# Fastino_FPGA_Supply.net
KiCad netlist of a schematic drawn in Altium Designer
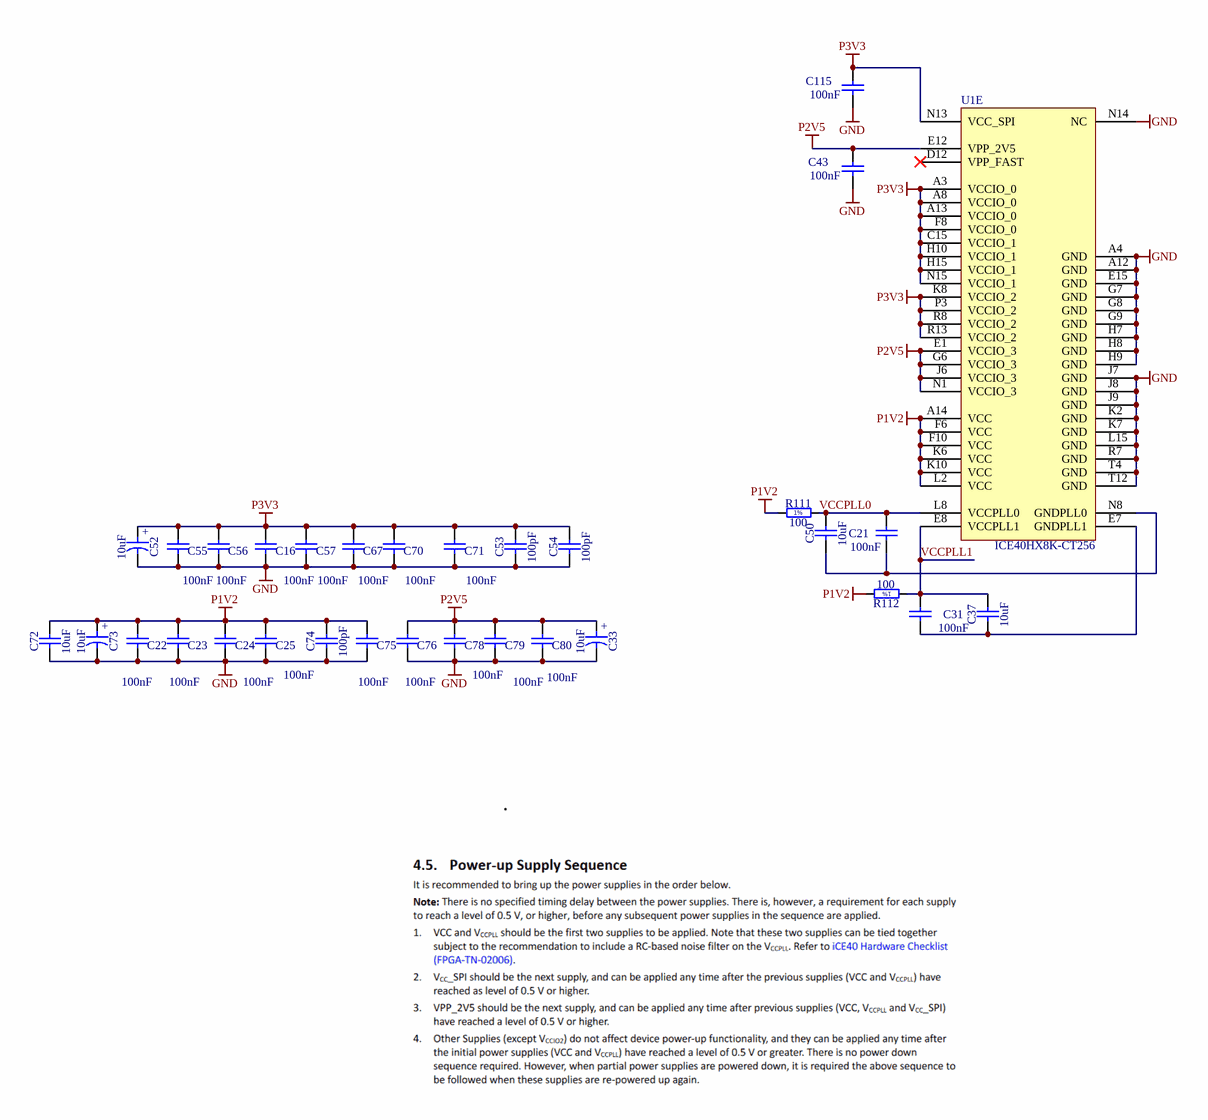
[diagram p0: Fastino_FPGA_Supply.SchDoc]

(export (version "E")
  (design (tool "Eeschema 10.0.6"))
  (components
    (comp (ref "C16")
      (value "100nF")
      (footprint "CAPC1005X55N")
      (description "Non-polarised capacitor")
      (fields
        (field (name "PART NUMBER") "CC0402_100NF_16V_10%_X5R")
        (field (name "VOLTAGE") "16V")
        (field (name "AUTHOR") "CERN DEM JLC")
      )
      (libsource (lib "Capacitors") (part "Capacitor - non polarized"))
    )
    (comp (ref "C21")
      (value "100nF")
      (footprint "CAPC1005X55N")
      (description "Non-polarised capacitor")
      (fields
        (field (name "PART NUMBER") "CC0402_100NF_16V_10%_X5R")
        (field (name "VOLTAGE") "16V")
        (field (name "AUTHOR") "CERN DEM JLC")
      )
      (libsource (lib "Capacitors") (part "Capacitor - non polarized"))
    )
    (comp (ref "C22")
      (value "100nF")
      (footprint "CAPC1005X55N")
      (description "Non-polarised capacitor")
      (fields
        (field (name "PART NUMBER") "CC0402_100NF_16V_10%_X5R")
        (field (name "VOLTAGE") "16V")
        (field (name "AUTHOR") "CERN DEM JLC")
      )
      (libsource (lib "Capacitors") (part "Capacitor - non polarized"))
    )
    (comp (ref "C23")
      (value "100nF")
      (footprint "CAPC1005X55N")
      (description "Non-polarised capacitor")
      (fields
        (field (name "PART NUMBER") "CC0402_100NF_16V_10%_X5R")
        (field (name "VOLTAGE") "16V")
        (field (name "AUTHOR") "CERN DEM JLC")
      )
      (libsource (lib "Capacitors") (part "Capacitor - non polarized"))
    )
    (comp (ref "C24")
      (value "100nF")
      (footprint "CAPC1005X55N")
      (description "Non-polarised capacitor")
      (fields
        (field (name "PART NUMBER") "CC0402_100NF_16V_10%_X5R")
        (field (name "VOLTAGE") "16V")
        (field (name "AUTHOR") "CERN DEM JLC")
      )
      (libsource (lib "Capacitors") (part "Capacitor - non polarized"))
    )
    (comp (ref "C25")
      (value "100nF")
      (footprint "CAPC1005X55N")
      (description "Non-polarised capacitor")
      (fields
        (field (name "PART NUMBER") "CC0402_100NF_16V_10%_X5R")
        (field (name "VOLTAGE") "16V")
        (field (name "AUTHOR") "CERN DEM JLC")
      )
      (libsource (lib "Capacitors") (part "Capacitor - non polarized"))
    )
    (comp (ref "C31")
      (value "100nF")
      (footprint "CAPC1005X55N")
      (description "Non-polarised capacitor")
      (fields
        (field (name "PART NUMBER") "CC0402_100NF_16V_10%_X5R")
        (field (name "VOLTAGE") "16V")
        (field (name "AUTHOR") "CERN DEM JLC")
      )
      (libsource (lib "Capacitors") (part "Capacitor - non polarized"))
    )
    (comp (ref "C33")
      (value "10uF")
      (footprint "CAPMP3216X180N")
      (description "Polarised capacitor")
      (fields
        (field (name "PART NUMBER") "CTE3216-18_10UF_16V_20%_AVX_TCJ")
        (field (name "VOLTAGE") "16V")
        (field (name "AUTHOR") "CERN DEM JLC")
      )
      (libsource (lib "Capacitors") (part "Capacitor - polarized"))
    )
    (comp (ref "C37")
      (value "10uF")
      (footprint "CAPC1005X70N")
      (description "Non-polarised capacitor")
      (fields
        (field (name "PART NUMBER") "CC0402_10UF_6.3V_20%_X5R")
        (field (name "VOLTAGE") "6.3V")
        (field (name "AUTHOR") "CERN DEM JLC")
      )
      (libsource (lib "Capacitors") (part "Capacitor - non polarized"))
    )
    (comp (ref "C43")
      (value "100nF")
      (footprint "CAPC1005X55N")
      (description "Non-polarised capacitor")
      (fields
        (field (name "PART NUMBER") "CC0402_100NF_16V_10%_X5R")
        (field (name "VOLTAGE") "16V")
        (field (name "AUTHOR") "CERN DEM JLC")
      )
      (libsource (lib "Capacitors") (part "Capacitor - non polarized"))
    )
    (comp (ref "C50")
      (value "10uF")
      (footprint "CAPC1005X70N")
      (description "Non-polarised capacitor")
      (fields
        (field (name "PART NUMBER") "CC0402_10UF_6.3V_20%_X5R")
        (field (name "VOLTAGE") "6.3V")
        (field (name "AUTHOR") "CERN DEM JLC")
      )
      (libsource (lib "Capacitors") (part "Capacitor - non polarized"))
    )
    (comp (ref "C52")
      (value "10uF")
      (footprint "CAPMP3216X180N")
      (description "Polarised capacitor")
      (fields
        (field (name "PART NUMBER") "CTE3216-18_10UF_16V_20%_AVX_TCJ")
        (field (name "VOLTAGE") "16V")
        (field (name "AUTHOR") "CERN DEM JLC")
      )
      (libsource (lib "Capacitors") (part "Capacitor - polarized"))
    )
    (comp (ref "C53")
      (value "100pF")
      (footprint "CAPC1005X55N")
      (description "Non-polarised capacitor")
      (fields
        (field (name "PART NUMBER") "CC0402_100PF_50V_5%_C0G")
        (field (name "VOLTAGE") "50V")
        (field (name "AUTHOR") "CERN DEM JLC")
      )
      (libsource (lib "Capacitors") (part "Capacitor - non polarized"))
    )
    (comp (ref "C54")
      (value "100pF")
      (footprint "CAPC1005X55N")
      (description "Non-polarised capacitor")
      (fields
        (field (name "PART NUMBER") "CC0402_100PF_50V_5%_C0G")
        (field (name "VOLTAGE") "50V")
        (field (name "AUTHOR") "CERN DEM JLC")
      )
      (libsource (lib "Capacitors") (part "Capacitor - non polarized"))
    )
    (comp (ref "C55")
      (value "100nF")
      (footprint "CAPC1005X55N")
      (description "Non-polarised capacitor")
      (fields
        (field (name "PART NUMBER") "CC0402_100NF_16V_10%_X5R")
        (field (name "VOLTAGE") "16V")
        (field (name "AUTHOR") "CERN DEM JLC")
      )
      (libsource (lib "Capacitors") (part "Capacitor - non polarized"))
    )
    (comp (ref "C56")
      (value "100nF")
      (footprint "CAPC1005X55N")
      (description "Non-polarised capacitor")
      (fields
        (field (name "PART NUMBER") "CC0402_100NF_16V_10%_X5R")
        (field (name "VOLTAGE") "16V")
        (field (name "AUTHOR") "CERN DEM JLC")
      )
      (libsource (lib "Capacitors") (part "Capacitor - non polarized"))
    )
    (comp (ref "C57")
      (value "100nF")
      (footprint "CAPC1005X55N")
      (description "Non-polarised capacitor")
      (fields
        (field (name "PART NUMBER") "CC0402_100NF_16V_10%_X5R")
        (field (name "VOLTAGE") "16V")
        (field (name "AUTHOR") "CERN DEM JLC")
      )
      (libsource (lib "Capacitors") (part "Capacitor - non polarized"))
    )
    (comp (ref "C67")
      (value "100nF")
      (footprint "CAPC1005X55N")
      (description "Non-polarised capacitor")
      (fields
        (field (name "PART NUMBER") "CC0402_100NF_16V_10%_X5R")
        (field (name "VOLTAGE") "16V")
        (field (name "AUTHOR") "CERN DEM JLC")
      )
      (libsource (lib "Capacitors") (part "Capacitor - non polarized"))
    )
    (comp (ref "C70")
      (value "100nF")
      (footprint "CAPC1005X55N")
      (description "Non-polarised capacitor")
      (fields
        (field (name "PART NUMBER") "CC0402_100NF_16V_10%_X5R")
        (field (name "VOLTAGE") "16V")
        (field (name "AUTHOR") "CERN DEM JLC")
      )
      (libsource (lib "Capacitors") (part "Capacitor - non polarized"))
    )
    (comp (ref "C71")
      (value "100nF")
      (footprint "CAPC1005X55N")
      (description "Non-polarised capacitor")
      (fields
        (field (name "PART NUMBER") "CC0402_100NF_16V_10%_X5R")
        (field (name "VOLTAGE") "16V")
        (field (name "AUTHOR") "CERN DEM JLC")
      )
      (libsource (lib "Capacitors") (part "Capacitor - non polarized"))
    )
    (comp (ref "C72")
      (value "10uF")
      (footprint "CAPC2012X135N")
      (description "Non-polarised capacitor")
      (fields
        (field (name "PART NUMBER") "CC0805_10UF_16V_10%_X5R")
        (field (name "VOLTAGE") "16V")
        (field (name "AUTHOR") "CERN DEM JLC")
      )
      (libsource (lib "Capacitors") (part "Capacitor - non polarized"))
    )
    (comp (ref "C73")
      (value "10uF")
      (footprint "CAPMP3216X180N")
      (description "Polarised capacitor")
      (fields
        (field (name "PART NUMBER") "CTE3216-18_10UF_16V_20%_AVX_TCJ")
        (field (name "VOLTAGE") "16V")
        (field (name "AUTHOR") "CERN DEM JLC")
      )
      (libsource (lib "Capacitors") (part "Capacitor - polarized"))
    )
    (comp (ref "C74")
      (value "100pF")
      (footprint "CAPC1005X55N")
      (description "Non-polarised capacitor")
      (fields
        (field (name "PART NUMBER") "CC0402_100PF_50V_5%_C0G")
        (field (name "VOLTAGE") "50V")
        (field (name "AUTHOR") "CERN DEM JLC")
      )
      (libsource (lib "Capacitors") (part "Capacitor - non polarized"))
    )
    (comp (ref "C75")
      (value "100nF")
      (footprint "CAPC1005X55N")
      (description "Non-polarised capacitor")
      (fields
        (field (name "PART NUMBER") "CC0402_100NF_16V_10%_X5R")
        (field (name "VOLTAGE") "16V")
        (field (name "AUTHOR") "CERN DEM JLC")
      )
      (libsource (lib "Capacitors") (part "Capacitor - non polarized"))
    )
    (comp (ref "C76")
      (value "100nF")
      (footprint "CAPC1005X55N")
      (description "Non-polarised capacitor")
      (fields
        (field (name "PART NUMBER") "CC0402_100NF_16V_10%_X5R")
        (field (name "VOLTAGE") "16V")
        (field (name "AUTHOR") "CERN DEM JLC")
      )
      (libsource (lib "Capacitors") (part "Capacitor - non polarized"))
    )
    (comp (ref "C78")
      (value "100nF")
      (footprint "CAPC1005X55N")
      (description "Non-polarised capacitor")
      (fields
        (field (name "PART NUMBER") "CC0402_100NF_16V_10%_X5R")
        (field (name "VOLTAGE") "16V")
        (field (name "AUTHOR") "CERN DEM JLC")
      )
      (libsource (lib "Capacitors") (part "Capacitor - non polarized"))
    )
    (comp (ref "C79")
      (value "100nF")
      (footprint "CAPC1005X55N")
      (description "Non-polarised capacitor")
      (fields
        (field (name "PART NUMBER") "CC0402_100NF_16V_10%_X5R")
        (field (name "VOLTAGE") "16V")
        (field (name "AUTHOR") "CERN DEM JLC")
      )
      (libsource (lib "Capacitors") (part "Capacitor - non polarized"))
    )
    (comp (ref "C80")
      (value "100nF")
      (footprint "CAPC1005X55N")
      (description "Non-polarised capacitor")
      (fields
        (field (name "PART NUMBER") "CC0402_100NF_16V_10%_X5R")
        (field (name "VOLTAGE") "16V")
        (field (name "AUTHOR") "CERN DEM JLC")
      )
      (libsource (lib "Capacitors") (part "Capacitor - non polarized"))
    )
    (comp (ref "C115")
      (value "100nF")
      (footprint "CAPC1005X55N")
      (description "Non-polarised capacitor")
      (fields
        (field (name "PART NUMBER") "CC0402_100NF_16V_10%_X5R")
        (field (name "VOLTAGE") "16V")
        (field (name "AUTHOR") "CERN DEM JLC")
      )
      (libsource (lib "Capacitors") (part "Capacitor - non polarized"))
    )
    (comp (ref "R111")
      (value "100")
      (footprint "RESC1005X40N")
      (description "Resistor - 1%")
      (fields
        (field (name "PART NUMBER") "R0402_100R_1%_0.0625W_100PPM")
        (field (name "POWER") "0.0625W")
        (field (name "AUTHOR") "CERN DEM JLC")
      )
      (libsource (lib "Resistors") (part "Resistor - 1%"))
    )
    (comp (ref "R112")
      (value "100")
      (footprint "RESC1005X40N")
      (description "Resistor - 1%")
      (fields
        (field (name "PART NUMBER") "R0402_100R_1%_0.0625W_100PPM")
        (field (name "POWER") "0.0625W")
        (field (name "AUTHOR") "CERN DEM JLC")
      )
      (libsource (lib "Resistors") (part "Resistor - 1%"))
    )
    (comp (ref "U1")
      (value "ICE40HX8K-CT256")
      (footprint "LATC-caBGA-256")
      (fields (field (name "MANUFACTURER") "Lattice Semiconductor"))
      (libsource (lib "Altium Content Vault") (part "LATC-HX8K-caBGA-256"))
    )
  )
  (nets
    (net (code "1") (name "/VCCPLL0") (class "Default")
      (node (ref "C21") (pin "2") (pinfunction "2_2") (pintype "passive"))
      (node (ref "C50") (pin "2") (pinfunction "2_2") (pintype "passive"))
      (node (ref "R111") (pin "2") (pinfunction "2_2") (pintype "passive"))
      (node (ref "U1") (pin "L8") (pinfunction "VCCPLL0_L8") (pintype "power_in"))
    )
    (net (code "2") (name "/VCCPLL1") (class "Default")
      (node (ref "C31") (pin "2") (pinfunction "2_2") (pintype "passive"))
      (node (ref "C37") (pin "2") (pinfunction "2_2") (pintype "passive"))
      (node (ref "R112") (pin "1") (pinfunction "1_1") (pintype "passive"))
      (node (ref "U1") (pin "E8") (pinfunction "VCCPLL1_E8") (pintype "power_in"))
    )
    (net (code "3") (name "GND") (class "Default")
      (node (ref "C115") (pin "1") (pinfunction "1_1") (pintype "passive"))
      (node (ref "C16") (pin "1") (pinfunction "1_1") (pintype "passive"))
      (node (ref "C22") (pin "1") (pinfunction "1_1") (pintype "passive"))
      (node (ref "C23") (pin "1") (pinfunction "1_1") (pintype "passive"))
      (node (ref "C24") (pin "1") (pinfunction "1_1") (pintype "passive"))
      (node (ref "C25") (pin "1") (pinfunction "1_1") (pintype "passive"))
      (node (ref "C33") (pin "2") (pinfunction "2_2") (pintype "passive"))
      (node (ref "C43") (pin "1") (pinfunction "1_1") (pintype "passive"))
      (node (ref "C52") (pin "2") (pinfunction "2_2") (pintype "passive"))
      (node (ref "C53") (pin "1") (pinfunction "1_1") (pintype "passive"))
      (node (ref "C54") (pin "1") (pinfunction "1_1") (pintype "passive"))
      (node (ref "C55") (pin "1") (pinfunction "1_1") (pintype "passive"))
      (node (ref "C56") (pin "1") (pinfunction "1_1") (pintype "passive"))
      (node (ref "C57") (pin "1") (pinfunction "1_1") (pintype "passive"))
      (node (ref "C67") (pin "1") (pinfunction "1_1") (pintype "passive"))
      (node (ref "C70") (pin "1") (pinfunction "1_1") (pintype "passive"))
      (node (ref "C71") (pin "1") (pinfunction "1_1") (pintype "passive"))
      (node (ref "C72") (pin "1") (pinfunction "1_1") (pintype "passive"))
      (node (ref "C73") (pin "2") (pinfunction "2_2") (pintype "passive"))
      (node (ref "C74") (pin "1") (pinfunction "1_1") (pintype "passive"))
      (node (ref "C75") (pin "1") (pinfunction "1_1") (pintype "passive"))
      (node (ref "C76") (pin "1") (pinfunction "1_1") (pintype "passive"))
      (node (ref "C78") (pin "1") (pinfunction "1_1") (pintype "passive"))
      (node (ref "C79") (pin "1") (pinfunction "1_1") (pintype "passive"))
      (node (ref "C80") (pin "1") (pinfunction "1_1") (pintype "passive"))
      (node (ref "U1") (pin "A12") (pinfunction "GND_A12") (pintype "power_in"))
      (node (ref "U1") (pin "A4") (pinfunction "GND_A4") (pintype "power_in"))
      (node (ref "U1") (pin "E15") (pinfunction "GND_E15") (pintype "power_in"))
      (node (ref "U1") (pin "G7") (pinfunction "GND_G7") (pintype "power_in"))
      (node (ref "U1") (pin "G8") (pinfunction "GND_G8") (pintype "power_in"))
      (node (ref "U1") (pin "G9") (pinfunction "GND_G9") (pintype "power_in"))
      (node (ref "U1") (pin "H7") (pinfunction "GND_H7") (pintype "power_in"))
      (node (ref "U1") (pin "H8") (pinfunction "GND_H8") (pintype "power_in"))
      (node (ref "U1") (pin "H9") (pinfunction "GND_H9") (pintype "power_in"))
      (node (ref "U1") (pin "J7") (pinfunction "GND_J7") (pintype "power_in"))
      (node (ref "U1") (pin "J8") (pinfunction "GND_J8") (pintype "power_in"))
      (node (ref "U1") (pin "J9") (pinfunction "GND_J9") (pintype "power_in"))
      (node (ref "U1") (pin "K2") (pinfunction "GND_K2") (pintype "power_in"))
      (node (ref "U1") (pin "K7") (pinfunction "GND_K7") (pintype "power_in"))
      (node (ref "U1") (pin "L15") (pinfunction "GND_L15") (pintype "power_in"))
      (node (ref "U1") (pin "N14") (pinfunction "NC_N14") (pintype "passive"))
      (node (ref "U1") (pin "R7") (pinfunction "GND_R7") (pintype "power_in"))
      (node (ref "U1") (pin "T12") (pinfunction "GND_T12") (pintype "power_in"))
      (node (ref "U1") (pin "T4") (pinfunction "GND_T4") (pintype "power_in"))
    )
    (net (code "4") (name "Net-(U1E-GNDPLL0)") (class "Default")
      (node (ref "C21") (pin "1") (pinfunction "1_1") (pintype "passive"))
      (node (ref "C50") (pin "1") (pinfunction "1_1") (pintype "passive"))
      (node (ref "U1") (pin "N8") (pinfunction "GNDPLL0_N8") (pintype "power_in"))
    )
    (net (code "5") (name "Net-(U1E-GNDPLL1)") (class "Default")
      (node (ref "C31") (pin "1") (pinfunction "1_1") (pintype "passive"))
      (node (ref "C37") (pin "1") (pinfunction "1_1") (pintype "passive"))
      (node (ref "U1") (pin "E7") (pinfunction "GNDPLL1_E7") (pintype "power_in"))
    )
    (net (code "6") (name "P1V2") (class "Default")
      (node (ref "C22") (pin "2") (pinfunction "2_2") (pintype "passive"))
      (node (ref "C23") (pin "2") (pinfunction "2_2") (pintype "passive"))
      (node (ref "C24") (pin "2") (pinfunction "2_2") (pintype "passive"))
      (node (ref "C25") (pin "2") (pinfunction "2_2") (pintype "passive"))
      (node (ref "C72") (pin "2") (pinfunction "2_2") (pintype "passive"))
      (node (ref "C73") (pin "1") (pinfunction "1_1") (pintype "passive"))
      (node (ref "C74") (pin "2") (pinfunction "2_2") (pintype "passive"))
      (node (ref "C75") (pin "2") (pinfunction "2_2") (pintype "passive"))
      (node (ref "R111") (pin "1") (pinfunction "1_1") (pintype "passive"))
      (node (ref "R112") (pin "2") (pinfunction "2_2") (pintype "passive"))
      (node (ref "U1") (pin "A14") (pinfunction "VCC_A14") (pintype "power_in"))
      (node (ref "U1") (pin "F10") (pinfunction "VCC_F10") (pintype "power_in"))
      (node (ref "U1") (pin "F6") (pinfunction "VCC_F6") (pintype "power_in"))
      (node (ref "U1") (pin "K10") (pinfunction "VCC_K10") (pintype "power_in"))
      (node (ref "U1") (pin "K6") (pinfunction "VCC_K6") (pintype "power_in"))
      (node (ref "U1") (pin "L2") (pinfunction "VCC_L2") (pintype "power_in"))
    )
    (net (code "7") (name "P2V5") (class "Default")
      (node (ref "C33") (pin "1") (pinfunction "1_1") (pintype "passive"))
      (node (ref "C43") (pin "2") (pinfunction "2_2") (pintype "passive"))
      (node (ref "C76") (pin "2") (pinfunction "2_2") (pintype "passive"))
      (node (ref "C78") (pin "2") (pinfunction "2_2") (pintype "passive"))
      (node (ref "C79") (pin "2") (pinfunction "2_2") (pintype "passive"))
      (node (ref "C80") (pin "2") (pinfunction "2_2") (pintype "passive"))
      (node (ref "U1") (pin "E1") (pinfunction "VCCIO_3_E1") (pintype "power_in"))
      (node (ref "U1") (pin "E12") (pinfunction "VPP_2V5_E12") (pintype "power_in"))
      (node (ref "U1") (pin "G6") (pinfunction "VCCIO_3_G6") (pintype "power_in"))
      (node (ref "U1") (pin "J6") (pinfunction "VCCIO_3_J6") (pintype "power_in"))
      (node (ref "U1") (pin "N1") (pinfunction "VCCIO_3_N1") (pintype "power_in"))
    )
    (net (code "8") (name "P3V3") (class "Default")
      (node (ref "C115") (pin "2") (pinfunction "2_2") (pintype "passive"))
      (node (ref "C16") (pin "2") (pinfunction "2_2") (pintype "passive"))
      (node (ref "C52") (pin "1") (pinfunction "1_1") (pintype "passive"))
      (node (ref "C53") (pin "2") (pinfunction "2_2") (pintype "passive"))
      (node (ref "C54") (pin "2") (pinfunction "2_2") (pintype "passive"))
      (node (ref "C55") (pin "2") (pinfunction "2_2") (pintype "passive"))
      (node (ref "C56") (pin "2") (pinfunction "2_2") (pintype "passive"))
      (node (ref "C57") (pin "2") (pinfunction "2_2") (pintype "passive"))
      (node (ref "C67") (pin "2") (pinfunction "2_2") (pintype "passive"))
      (node (ref "C70") (pin "2") (pinfunction "2_2") (pintype "passive"))
      (node (ref "C71") (pin "2") (pinfunction "2_2") (pintype "passive"))
      (node (ref "U1") (pin "A13") (pinfunction "VCCIO_0_A13") (pintype "power_in"))
      (node (ref "U1") (pin "A3") (pinfunction "VCCIO_0_A3") (pintype "power_in"))
      (node (ref "U1") (pin "A8") (pinfunction "VCCIO_0_A8") (pintype "power_in"))
      (node (ref "U1") (pin "C15") (pinfunction "VCCIO_1_C15") (pintype "power_in"))
      (node (ref "U1") (pin "F8") (pinfunction "VCCIO_0_F8") (pintype "power_in"))
      (node (ref "U1") (pin "H10") (pinfunction "VCCIO_1_H10") (pintype "power_in"))
      (node (ref "U1") (pin "H15") (pinfunction "VCCIO_1_H15") (pintype "power_in"))
      (node (ref "U1") (pin "K8") (pinfunction "VCCIO_2_K8") (pintype "power_in"))
      (node (ref "U1") (pin "N13") (pinfunction "VCC_SPI_N13") (pintype "power_in"))
      (node (ref "U1") (pin "N15") (pinfunction "VCCIO_1_N15") (pintype "power_in"))
      (node (ref "U1") (pin "P3") (pinfunction "VCCIO_2_P3") (pintype "power_in"))
      (node (ref "U1") (pin "R13") (pinfunction "VCCIO_2_R13") (pintype "power_in"))
      (node (ref "U1") (pin "R8") (pinfunction "VCCIO_2_R8") (pintype "power_in"))
    )
    (net (code "9") (name "unconnected-(U1E-VPP_FAST-PadD12)") (class "Default")
      (node (ref "U1") (pin "D12") (pinfunction "VPP_FAST_D12") (pintype "power_in+no_connect"))
    )
  )
)
